# 2011_CARTE_PUISSANCE.net
KiCad netlist of a schematic drawn in Altium Designer
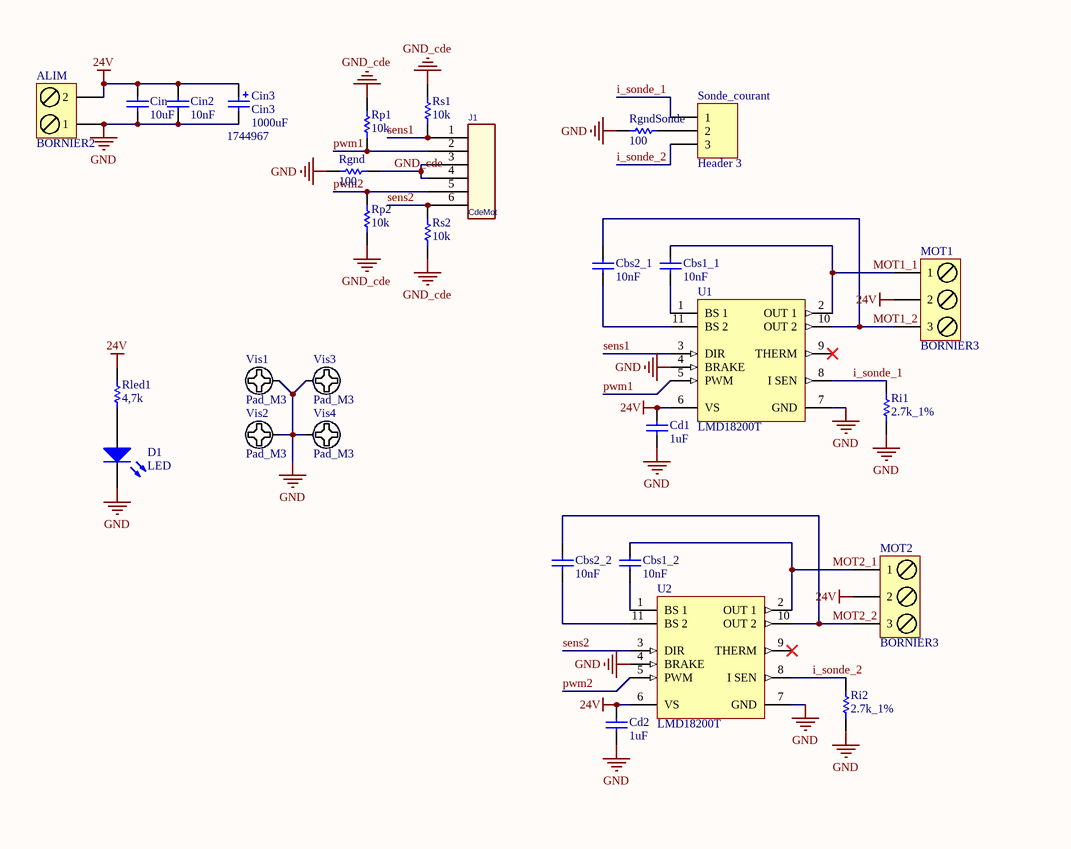
[diagram p0: 2011_CARTE_PUISSANCE.SchDoc, left]
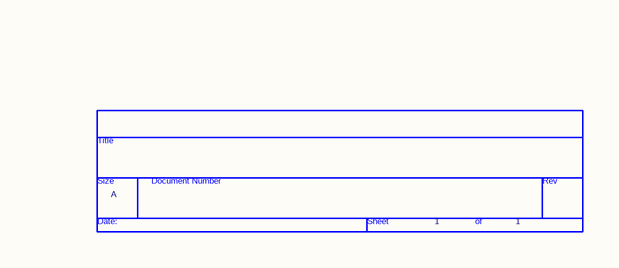
[diagram p1: 2011_CARTE_PUISSANCE.SchDoc, right]

(export (version "E")
  (design (tool "Eeschema 10.0.6"))
  (components
    (comp (ref "*")
      (value "TitleBlock0")
      (fields (field (name "PAGE COUNT") "1") (field (name "PAGE NUMBER") "1") (field (name "PAGE SIZE") "A"))
      (libsource (lib "*") (part "TitleBlock0"))
    )
    (comp (ref "ALIM")
      (value "BORNIER2")
      (footprint "BORNIER2")
      (description "Terminal blocks, 2 pins, pitch=5mm")
      (libsource (lib "Robot2010") (part "BORNIER2"))
    )
    (comp (ref "Cbs1_1")
      (value "10nF")
      (footprint "C0805_N")
      (description "Capacitor")
      (fields (field (name "PUBLISHER") "Altium Limited"))
      (libsource (lib "DG_Condensateur") (part "Capacitor"))
    )
    (comp (ref "Cbs1_2")
      (value "10nF")
      (footprint "C0805_N")
      (description "Capacitor")
      (fields (field (name "PUBLISHER") "Altium Limited"))
      (libsource (lib "DG_Condensateur") (part "Capacitor"))
    )
    (comp (ref "Cbs2_1")
      (value "10nF")
      (footprint "C0805_N")
      (description "Capacitor")
      (fields (field (name "PUBLISHER") "Altium Limited"))
      (libsource (lib "DG_Condensateur") (part "Capacitor"))
    )
    (comp (ref "Cbs2_2")
      (value "10nF")
      (footprint "C0805_N")
      (description "Capacitor")
      (fields (field (name "PUBLISHER") "Altium Limited"))
      (libsource (lib "DG_Condensateur") (part "Capacitor"))
    )
    (comp (ref "Cd1")
      (value "1uF")
      (footprint "C1206_N")
      (description "Capacitor")
      (fields (field (name "PUBLISHER") "Altium Limited"))
      (libsource (lib "DG_Condensateur") (part "Capacitor"))
    )
    (comp (ref "Cd2")
      (value "1uF")
      (footprint "C1206_N")
      (description "Capacitor")
      (fields (field (name "PUBLISHER") "Altium Limited"))
      (libsource (lib "DG_Condensateur") (part "Capacitor"))
    )
    (comp (ref "Cin")
      (value "10uF")
      (footprint "C1206_N")
      (description "Capacitor")
      (fields (field (name "PUBLISHER") "Altium Limited"))
      (libsource (lib "DG_Condensateur") (part "Capacitor"))
    )
    (comp (ref "Cin2")
      (value "10nF")
      (footprint "C0805_N")
      (description "Capacitor")
      (fields (field (name "PUBLISHER") "Altium Limited"))
      (libsource (lib "DG_Condensateur") (part "Capacitor"))
    )
    (comp (ref "Cin3")
      (value "Cin3")
      (footprint "COND_POL_RAD_5.08B")
      (description "Polarized Capacitor")
      (fields
        (field (name "ALTIUM_VALUE") "1000uF")
        (field (name "FAR") "1744967")
        (field (name "PUBLISHER") "Altium Limited")
      )
      (libsource (lib "Robot2010") (part "CONDENSATEUR_POLARISE"))
    )
    (comp (ref "D1")
      (value "LED")
      (footprint "LED_3mm")
      (description "Typical LED")
      (fields (field (name "PUBLISHER") "Altium Limited"))
      (libsource (lib "DG_LED") (part "LED"))
    )
    (comp (ref "J1") (value "CdeMot") (footprint "RJ11_6/6") (libsource (lib "*") (part "CONNECTEUR_RJ12")))
    (comp (ref "MOT1")
      (value "BORNIER3")
      (footprint "BORNIER3")
      (description "Terminal blocks, 2 pins, pitch=5mm")
      (libsource (lib "Robot2010") (part "BORNIER3"))
    )
    (comp (ref "MOT2")
      (value "BORNIER3")
      (footprint "BORNIER3")
      (description "Terminal blocks, 2 pins, pitch=5mm")
      (libsource (lib "Robot2010") (part "BORNIER3"))
    )
    (comp (ref "Rgnd")
      (value "100")
      (footprint "R1206_N")
      (description "Resistor")
      (fields (field (name "PUBLISHER") "Altium Limited"))
      (libsource (lib "DG_Resistance") (part "Resistor"))
    )
    (comp (ref "RgndSonde")
      (value "100")
      (footprint "R1206_N")
      (description "Resistor")
      (fields (field (name "PUBLISHER") "Altium Limited"))
      (libsource (lib "DG_Resistance") (part "Resistor"))
    )
    (comp (ref "Ri1")
      (value "2.7k_1%")
      (footprint "R1206_N")
      (description "Resistor")
      (fields (field (name "PUBLISHER") "Altium Limited"))
      (libsource (lib "DG_Resistance") (part "Resistor"))
    )
    (comp (ref "Ri2")
      (value "2.7k_1%")
      (footprint "R1206_N")
      (description "Resistor")
      (fields (field (name "PUBLISHER") "Altium Limited"))
      (libsource (lib "DG_Resistance") (part "Resistor"))
    )
    (comp (ref "Rled1")
      (value "4,7k")
      (footprint "R1206_N")
      (description "Resistor")
      (fields (field (name "PUBLISHER") "Altium Limited"))
      (libsource (lib "DG_Resistance") (part "Resistor"))
    )
    (comp (ref "Rp1")
      (value "10k")
      (footprint "R1206_N")
      (description "Resistor")
      (fields (field (name "PUBLISHER") "Altium Limited"))
      (libsource (lib "DG_Resistance") (part "Resistor"))
    )
    (comp (ref "Rp2")
      (value "10k")
      (footprint "R1206_N")
      (description "Resistor")
      (fields (field (name "PUBLISHER") "Altium Limited"))
      (libsource (lib "DG_Resistance") (part "Resistor"))
    )
    (comp (ref "Rs1")
      (value "10k")
      (footprint "R1206_N")
      (description "Resistor")
      (fields (field (name "PUBLISHER") "Altium Limited"))
      (libsource (lib "DG_Resistance") (part "Resistor"))
    )
    (comp (ref "Rs2")
      (value "10k")
      (footprint "R1206_N")
      (description "Resistor")
      (fields (field (name "PUBLISHER") "Altium Limited"))
      (libsource (lib "DG_Resistance") (part "Resistor"))
    )
    (comp (ref "Sonde_courant")
      (value "Header 3")
      (footprint "HDR1X3")
      (description "Header, 3-Pin")
      (fields (field (name "PUBLISHER") "Altium Limited"))
      (libsource (lib "DG_Connecteur") (part "Header 3"))
    )
    (comp (ref "U1")
      (value "LMD18200T")
      (footprint "TA11B")
      (description "3A, 55V H-Bridge")
      (fields
        (field (name "MANUFACTURER") "National Semiconductor")
        (field (name "DIGIKEYPARTNUMBER") "LMD18200T-ND")
        (field (name "PUBLISHER") "Altium Limited")
      )
      (libsource (lib "NSC MiscPower") (part "LMD18200T"))
    )
    (comp (ref "U2")
      (value "LMD18200T")
      (footprint "TA11B")
      (description "3A, 55V H-Bridge")
      (fields
        (field (name "MANUFACTURER") "National Semiconductor")
        (field (name "DIGIKEYPARTNUMBER") "LMD18200T-ND")
        (field (name "PUBLISHER") "Altium Limited")
      )
      (libsource (lib "NSC MiscPower") (part "LMD18200T"))
    )
    (comp (ref "Vis1")
      (value "Pad_M3")
      (footprint "M3x6mm")
      (description "Vis M3 X 6mm _TORX_Tête 6mm")
      (fields (field (name "PUBLISHER") "Damien Guitton"))
      (libsource (lib "DG_Mecanique") (part "Vis M3 X 6mm _TORX_Tête 6mm"))
    )
    (comp (ref "Vis2")
      (value "Pad_M3")
      (footprint "M3x6mm")
      (description "Vis M3 X 6mm _TORX_Tête 6mm")
      (fields (field (name "PUBLISHER") "Damien Guitton"))
      (libsource (lib "DG_Mecanique") (part "Vis M3 X 6mm _TORX_Tête 6mm"))
    )
    (comp (ref "Vis3")
      (value "Pad_M3")
      (footprint "M3x6mm")
      (description "Vis M3 X 6mm _TORX_Tête 6mm")
      (fields (field (name "PUBLISHER") "Damien Guitton"))
      (libsource (lib "DG_Mecanique") (part "Vis M3 X 6mm _TORX_Tête 6mm"))
    )
    (comp (ref "Vis4")
      (value "Pad_M3")
      (footprint "M3x6mm")
      (description "Vis M3 X 6mm _TORX_Tête 6mm")
      (fields (field (name "PUBLISHER") "Damien Guitton"))
      (libsource (lib "DG_Mecanique") (part "Vis M3 X 6mm _TORX_Tête 6mm"))
    )
  )
  (nets
    (net (code "1") (name "/MOT1_1") (class "Default")
      (node (ref "Cbs1_1") (pin "2") (pinfunction "2_2") (pintype "passive"))
      (node (ref "MOT1") (pin "1") (pinfunction "1_1") (pintype "passive"))
      (node (ref "U1") (pin "2") (pinfunction "OUT_1_2") (pintype "output"))
    )
    (net (code "2") (name "/MOT1_2") (class "Default")
      (node (ref "Cbs2_1") (pin "2") (pinfunction "2_2") (pintype "passive"))
      (node (ref "MOT1") (pin "3") (pinfunction "3_3") (pintype "passive"))
      (node (ref "U1") (pin "10") (pinfunction "OUT_2_10") (pintype "output"))
    )
    (net (code "3") (name "/MOT2_1") (class "Default")
      (node (ref "Cbs1_2") (pin "2") (pinfunction "2_2") (pintype "passive"))
      (node (ref "MOT2") (pin "1") (pinfunction "1_1") (pintype "passive"))
      (node (ref "U2") (pin "2") (pinfunction "OUT_1_2") (pintype "output"))
    )
    (net (code "4") (name "/MOT2_2") (class "Default")
      (node (ref "Cbs2_2") (pin "2") (pinfunction "2_2") (pintype "passive"))
      (node (ref "MOT2") (pin "3") (pinfunction "3_3") (pintype "passive"))
      (node (ref "U2") (pin "10") (pinfunction "OUT_2_10") (pintype "output"))
    )
    (net (code "5") (name "/i_sonde_1") (class "Default")
      (node (ref "Ri1") (pin "1") (pinfunction "1_1") (pintype "passive"))
      (node (ref "Sonde_courant") (pin "1") (pinfunction "1_1") (pintype "passive"))
      (node (ref "U1") (pin "8") (pinfunction "I_SEN_8") (pintype "output"))
    )
    (net (code "6") (name "/i_sonde_2") (class "Default")
      (node (ref "Ri2") (pin "1") (pinfunction "1_1") (pintype "passive"))
      (node (ref "Sonde_courant") (pin "3") (pinfunction "3_3") (pintype "passive"))
      (node (ref "U2") (pin "8") (pinfunction "I_SEN_8") (pintype "output"))
    )
    (net (code "7") (name "/pwm1") (class "Default")
      (node (ref "J1") (pin "2") (pinfunction "2_2") (pintype "passive"))
      (node (ref "Rp1") (pin "1") (pinfunction "1_1") (pintype "passive"))
      (node (ref "U1") (pin "5") (pinfunction "PWM_5") (pintype "input"))
    )
    (net (code "8") (name "/pwm2") (class "Default")
      (node (ref "J1") (pin "5") (pinfunction "5_5") (pintype "passive"))
      (node (ref "Rp2") (pin "2") (pinfunction "2_2") (pintype "passive"))
      (node (ref "U2") (pin "5") (pinfunction "PWM_5") (pintype "input"))
    )
    (net (code "9") (name "/sens1") (class "Default")
      (node (ref "J1") (pin "1") (pinfunction "1_1") (pintype "passive"))
      (node (ref "Rs1") (pin "1") (pinfunction "1_1") (pintype "passive"))
      (node (ref "U1") (pin "3") (pinfunction "DIR_3") (pintype "input"))
    )
    (net (code "10") (name "/sens2") (class "Default")
      (node (ref "J1") (pin "6") (pinfunction "6_6") (pintype "passive"))
      (node (ref "Rs2") (pin "2") (pinfunction "2_2") (pintype "passive"))
      (node (ref "U2") (pin "3") (pinfunction "DIR_3") (pintype "input"))
    )
    (net (code "11") (name "24V") (class "Default")
      (node (ref "ALIM") (pin "2") (pinfunction "2_2") (pintype "passive"))
      (node (ref "Cd1") (pin "1") (pinfunction "1_1") (pintype "passive"))
      (node (ref "Cd2") (pin "1") (pinfunction "1_1") (pintype "passive"))
      (node (ref "Cin") (pin "2") (pinfunction "2_2") (pintype "passive"))
      (node (ref "Cin2") (pin "2") (pinfunction "2_2") (pintype "passive"))
      (node (ref "Cin3") (pin "1") (pinfunction "1_1") (pintype "passive"))
      (node (ref "MOT1") (pin "2") (pinfunction "2_2") (pintype "passive"))
      (node (ref "MOT2") (pin "2") (pinfunction "2_2") (pintype "passive"))
      (node (ref "Rled1") (pin "2") (pinfunction "2_2") (pintype "passive"))
      (node (ref "U1") (pin "6") (pinfunction "VS_6") (pintype "power_in"))
      (node (ref "U2") (pin "6") (pinfunction "VS_6") (pintype "power_in"))
    )
    (net (code "12") (name "GND") (class "Default")
      (node (ref "ALIM") (pin "1") (pinfunction "1_1") (pintype "passive"))
      (node (ref "Cd1") (pin "2") (pinfunction "2_2") (pintype "passive"))
      (node (ref "Cd2") (pin "2") (pinfunction "2_2") (pintype "passive"))
      (node (ref "Cin") (pin "1") (pinfunction "1_1") (pintype "passive"))
      (node (ref "Cin2") (pin "1") (pinfunction "1_1") (pintype "passive"))
      (node (ref "Cin3") (pin "2") (pinfunction "2_2") (pintype "passive"))
      (node (ref "D1") (pin "2") (pinfunction "2_2") (pintype "passive"))
      (node (ref "Rgnd") (pin "2") (pinfunction "2_2") (pintype "passive"))
      (node (ref "RgndSonde") (pin "2") (pinfunction "2_2") (pintype "passive"))
      (node (ref "Ri1") (pin "2") (pinfunction "2_2") (pintype "passive"))
      (node (ref "Ri2") (pin "2") (pinfunction "2_2") (pintype "passive"))
      (node (ref "U1") (pin "4") (pinfunction "BRAKE_4") (pintype "input"))
      (node (ref "U1") (pin "7") (pinfunction "GND_7") (pintype "power_in"))
      (node (ref "U2") (pin "4") (pinfunction "BRAKE_4") (pintype "input"))
      (node (ref "U2") (pin "7") (pinfunction "GND_7") (pintype "power_in"))
      (node (ref "Vis1") (pin "1") (pinfunction "1_1") (pintype "passive"))
      (node (ref "Vis2") (pin "1") (pinfunction "1_1") (pintype "passive"))
      (node (ref "Vis3") (pin "1") (pinfunction "1_1") (pintype "passive"))
      (node (ref "Vis4") (pin "1") (pinfunction "1_1") (pintype "passive"))
    )
    (net (code "13") (name "GND_cde") (class "Default")
      (node (ref "J1") (pin "3") (pinfunction "3_3") (pintype "passive"))
      (node (ref "J1") (pin "4") (pinfunction "4_4") (pintype "passive"))
      (node (ref "Rgnd") (pin "1") (pinfunction "1_1") (pintype "passive"))
      (node (ref "Rp1") (pin "2") (pinfunction "2_2") (pintype "passive"))
      (node (ref "Rp2") (pin "1") (pinfunction "1_1") (pintype "passive"))
      (node (ref "Rs1") (pin "2") (pinfunction "2_2") (pintype "passive"))
      (node (ref "Rs2") (pin "1") (pinfunction "1_1") (pintype "passive"))
    )
    (net (code "14") (name "Net-(D1-Pad1)") (class "Default")
      (node (ref "D1") (pin "1") (pinfunction "1_1") (pintype "passive"))
      (node (ref "Rled1") (pin "1") (pinfunction "1_1") (pintype "passive"))
    )
    (net (code "15") (name "Net-(RgndSonde-Pad1)") (class "Default")
      (node (ref "RgndSonde") (pin "1") (pinfunction "1_1") (pintype "passive"))
      (node (ref "Sonde_courant") (pin "2") (pinfunction "2_2") (pintype "passive"))
    )
    (net (code "16") (name "Net-(U1-BS_1)") (class "Default")
      (node (ref "Cbs1_1") (pin "1") (pinfunction "1_1") (pintype "passive"))
      (node (ref "U1") (pin "1") (pinfunction "BS_1_1") (pintype "passive"))
    )
    (net (code "17") (name "Net-(U1-BS_2)") (class "Default")
      (node (ref "Cbs2_1") (pin "1") (pinfunction "1_1") (pintype "passive"))
      (node (ref "U1") (pin "11") (pinfunction "BS_2_11") (pintype "passive"))
    )
    (net (code "18") (name "Net-(U2-BS_1)") (class "Default")
      (node (ref "Cbs1_2") (pin "1") (pinfunction "1_1") (pintype "passive"))
      (node (ref "U2") (pin "1") (pinfunction "BS_1_1") (pintype "passive"))
    )
    (net (code "19") (name "Net-(U2-BS_2)") (class "Default")
      (node (ref "Cbs2_2") (pin "1") (pinfunction "1_1") (pintype "passive"))
      (node (ref "U2") (pin "11") (pinfunction "BS_2_11") (pintype "passive"))
    )
    (net (code "20") (name "unconnected-(U1-THERM-Pad9)") (class "Default")
      (node (ref "U1") (pin "9") (pinfunction "THERM_9") (pintype "output+no_connect"))
    )
    (net (code "21") (name "unconnected-(U2-THERM-Pad9)") (class "Default")
      (node (ref "U2") (pin "9") (pinfunction "THERM_9") (pintype "output+no_connect"))
    )
  )
)
